# NRF24L01_LCD5110.net
KiCad netlist of a schematic drawn in EAGLE
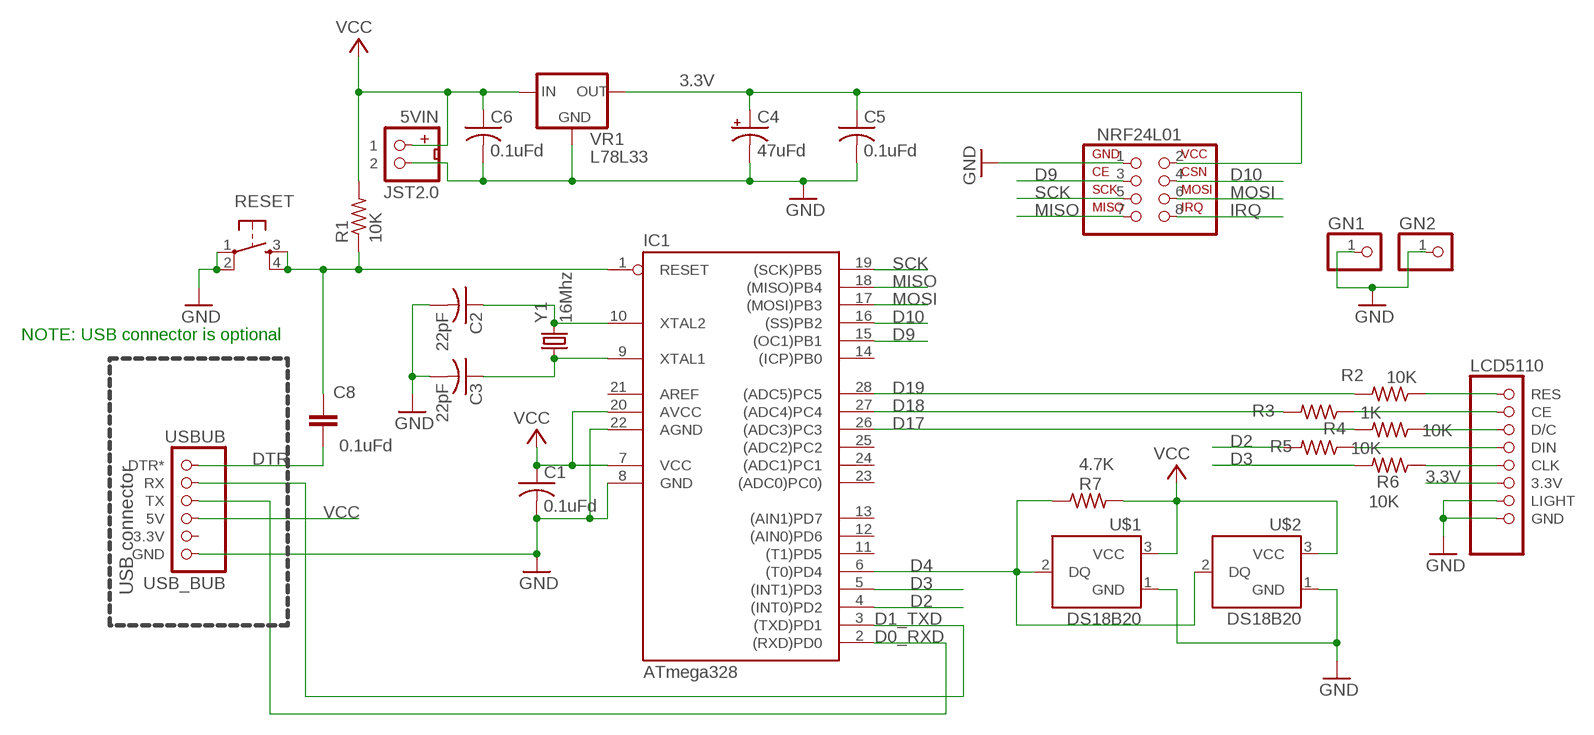
[diagram p0: schematic, sheet 1]

(export (version "E")
  (design (tool "Eeschema 10.0.6"))
  (components
    (comp (ref "5VIN")
      (value "JST2.0")
      (footprint "eagle-import:JST2.0")
      (libsource (lib "eagle-import") (part "JST2.0"))
    )
    (comp (ref "C1")
      (value "0.1uFd")
      (footprint "eagle-import:C050-025X075")
      (libsource (lib "eagle-import") (part "C-US050-025X075"))
    )
    (comp (ref "C2")
      (value "22pF")
      (footprint "eagle-import:C025-025X050")
      (libsource (lib "eagle-import") (part "C-US025-025X050"))
    )
    (comp (ref "C3")
      (value "22pF")
      (footprint "eagle-import:C025-025X050")
      (libsource (lib "eagle-import") (part "C-US025-025X050"))
    )
    (comp (ref "C4")
      (value "47uFd")
      (footprint "eagle-import:E2,5-6E")
      (libsource (lib "eagle-import") (part "CPOL-USE2,5-6E"))
    )
    (comp (ref "C5")
      (value "0.1uFd")
      (footprint "eagle-import:C025-025X050")
      (libsource (lib "eagle-import") (part "C-US025-025X050"))
    )
    (comp (ref "C6")
      (value "0.1uFd")
      (footprint "eagle-import:C050-025X075")
      (libsource (lib "eagle-import") (part "C-US050-025X075"))
    )
    (comp (ref "C8")
      (value "0.1uFd")
      (footprint "eagle-import:C050-025X075")
      (libsource (lib "eagle-import") (part "C-EU050-025X075"))
    )
    (comp (ref "GN1")
      (value "PINHD-1X1")
      (footprint "eagle-import:1X01")
      (libsource (lib "eagle-import") (part "PINHD-1X1"))
    )
    (comp (ref "GN2")
      (value "PINHD-1X1")
      (footprint "eagle-import:1X01")
      (libsource (lib "eagle-import") (part "PINHD-1X1"))
    )
    (comp (ref "IC1")
      (value "ATmega328")
      (footprint "eagle-import:DIL28-3")
      (libsource (lib "eagle-import") (part "AT90S4433P"))
    )
    (comp (ref "LCD5110")
      (value "LCD5110_1TOP")
      (footprint "eagle-import:LCD5110T1")
      (libsource (lib "eagle-import") (part "LCD5110_1TOP"))
    )
    (comp (ref "NRF24L01")
      (value "NRF24L01+")
      (footprint "eagle-import:NRF24L01+")
      (libsource (lib "eagle-import") (part "NRF24L01+"))
    )
    (comp (ref "R1")
      (value "10K")
      (footprint "eagle-import:0207_2V")
      (libsource (lib "eagle-import") (part "R-US_0207/2V"))
    )
    (comp (ref "R2")
      (value "10K")
      (footprint "eagle-import:0207_5V")
      (libsource (lib "eagle-import") (part "R-US_0207/5V"))
    )
    (comp (ref "R3")
      (value "1K")
      (footprint "eagle-import:0207_5V")
      (libsource (lib "eagle-import") (part "R-US_0207/5V"))
    )
    (comp (ref "R4")
      (value "10K")
      (footprint "eagle-import:0207_5V")
      (libsource (lib "eagle-import") (part "R-US_0207/5V"))
    )
    (comp (ref "R5")
      (value "10K")
      (footprint "eagle-import:0207_5V")
      (libsource (lib "eagle-import") (part "R-US_0207/5V"))
    )
    (comp (ref "R6")
      (value "10K")
      (footprint "eagle-import:0207_5V")
      (libsource (lib "eagle-import") (part "R-US_0207/5V"))
    )
    (comp (ref "R7")
      (value "4.7K")
      (footprint "eagle-import:0207_2V")
      (libsource (lib "eagle-import") (part "R-US_0207/2V"))
    )
    (comp (ref "RESET")
      (value "TAC_SWITCHPTH")
      (footprint "eagle-import:TACTILE-PTH")
      (libsource (lib "eagle-import") (part "TAC_SWITCHPTH"))
    )
    (comp (ref "U$1")
      (value "DS18B20")
      (footprint "eagle-import:DS18B20")
      (libsource (lib "eagle-import") (part "DS18B20"))
    )
    (comp (ref "U$2")
      (value "DS18B20")
      (footprint "eagle-import:DS18B20")
      (libsource (lib "eagle-import") (part "DS18B20"))
    )
    (comp (ref "USBUB")
      (value "USB_BUB")
      (footprint "eagle-import:USB_BUB")
      (libsource (lib "eagle-import") (part "USB_BUB"))
    )
    (comp (ref "VR1")
      (value "L78L33")
      (footprint "eagle-import:78LXX")
      (libsource (lib "eagle-import") (part "78LXX"))
    )
    (comp (ref "Y1")
      (value "16Mhz")
      (footprint "eagle-import:HC49US")
      (libsource (lib "eagle-import") (part "CRYSTALHC49US"))
    )
  )
  (nets
    (net (code "1") (name "/3.3V") (class "Default")
      (node (ref "C4") (pin "+") (pinfunction "+_+") (pintype "passive"))
      (node (ref "C5") (pin "1") (pinfunction "1_1") (pintype "passive"))
      (node (ref "LCD5110") (pin "3.3V") (pinfunction "3.3V_3.3V") (pintype "passive"))
      (node (ref "NRF24L01") (pin "2") (pinfunction "2_2") (pintype "passive"))
      (node (ref "VR1") (pin "OUT") (pinfunction "OUT_OUT") (pintype "passive"))
    )
    (net (code "2") (name "/D0_RXD") (class "Default")
      (node (ref "IC1") (pin "2") (pinfunction "(RXD)PD0_2") (pintype "bidirectional"))
      (node (ref "USBUB") (pin "TX") (pinfunction "TX_TX") (pintype "passive"))
    )
    (net (code "3") (name "/D1_TXD") (class "Default")
      (node (ref "IC1") (pin "3") (pinfunction "(TXD)PD1_3") (pintype "bidirectional"))
      (node (ref "USBUB") (pin "RX") (pinfunction "RX_RX") (pintype "passive"))
    )
    (net (code "4") (name "/D2") (class "Default")
      (node (ref "IC1") (pin "4") (pinfunction "(INT0)PD2_4") (pintype "bidirectional"))
      (node (ref "R5") (pin "2") (pinfunction "2_2") (pintype "passive"))
    )
    (net (code "5") (name "/D3") (class "Default")
      (node (ref "IC1") (pin "5") (pinfunction "(INT1)PD3_5") (pintype "bidirectional"))
      (node (ref "R6") (pin "2") (pinfunction "2_2") (pintype "passive"))
    )
    (net (code "6") (name "/D4") (class "Default")
      (node (ref "IC1") (pin "6") (pinfunction "(T0)PD4_6") (pintype "bidirectional"))
      (node (ref "R7") (pin "1") (pinfunction "1_1") (pintype "passive"))
      (node (ref "U$1") (pin "2") (pinfunction "DQ_2") (pintype "bidirectional"))
      (node (ref "U$2") (pin "2") (pinfunction "DQ_2") (pintype "bidirectional"))
    )
    (net (code "7") (name "/D9") (class "Default")
      (node (ref "IC1") (pin "15") (pinfunction "(OC1)PB1_15") (pintype "bidirectional"))
      (node (ref "NRF24L01") (pin "3") (pinfunction "3_3") (pintype "passive"))
    )
    (net (code "8") (name "/D10") (class "Default")
      (node (ref "IC1") (pin "16") (pinfunction "(SS)PB2_16") (pintype "bidirectional"))
      (node (ref "NRF24L01") (pin "4") (pinfunction "4_4") (pintype "passive"))
    )
    (net (code "9") (name "/D17") (class "Default")
      (node (ref "IC1") (pin "26") (pinfunction "(ADC3)PC3_26") (pintype "bidirectional"))
      (node (ref "R4") (pin "2") (pinfunction "2_2") (pintype "passive"))
    )
    (net (code "10") (name "/D18") (class "Default")
      (node (ref "IC1") (pin "27") (pinfunction "(ADC4)PC4_27") (pintype "bidirectional"))
      (node (ref "R3") (pin "2") (pinfunction "2_2") (pintype "passive"))
    )
    (net (code "11") (name "/D19") (class "Default")
      (node (ref "IC1") (pin "28") (pinfunction "(ADC5)PC5_28") (pintype "bidirectional"))
      (node (ref "R2") (pin "2") (pinfunction "2_2") (pintype "passive"))
    )
    (net (code "12") (name "/DTR") (class "Default")
      (node (ref "C8") (pin "1") (pinfunction "1_1") (pintype "passive"))
      (node (ref "USBUB") (pin "DTR*") (pinfunction "DTR*_DTR*") (pintype "passive"))
    )
    (net (code "13") (name "/IRQ") (class "Default")
      (node (ref "NRF24L01") (pin "8") (pinfunction "8_8") (pintype "passive"))
    )
    (net (code "14") (name "/MISO") (class "Default")
      (node (ref "IC1") (pin "18") (pinfunction "(MISO)PB4_18") (pintype "bidirectional"))
      (node (ref "NRF24L01") (pin "7") (pinfunction "7_7") (pintype "passive"))
    )
    (net (code "15") (name "/MOSI") (class "Default")
      (node (ref "IC1") (pin "17") (pinfunction "(MOSI)PB3_17") (pintype "bidirectional"))
      (node (ref "NRF24L01") (pin "6") (pinfunction "6_6") (pintype "passive"))
    )
    (net (code "16") (name "/SCK") (class "Default")
      (node (ref "IC1") (pin "19") (pinfunction "(SCK)PB5_19") (pintype "bidirectional"))
      (node (ref "NRF24L01") (pin "5") (pinfunction "5_5") (pintype "passive"))
    )
    (net (code "17") (name "GND") (class "Default")
      (node (ref "5VIN") (pin "2") (pinfunction "2_2") (pintype "passive"))
      (node (ref "C1") (pin "2") (pinfunction "2_2") (pintype "passive"))
      (node (ref "C2") (pin "2") (pinfunction "2_2") (pintype "passive"))
      (node (ref "C3") (pin "2") (pinfunction "2_2") (pintype "passive"))
      (node (ref "C4") (pin "-") (pinfunction "-_-") (pintype "passive"))
      (node (ref "C5") (pin "2") (pinfunction "2_2") (pintype "passive"))
      (node (ref "C6") (pin "2") (pinfunction "2_2") (pintype "passive"))
      (node (ref "GN1") (pin "1") (pinfunction "1_1") (pintype "passive"))
      (node (ref "GN2") (pin "1") (pinfunction "1_1") (pintype "passive"))
      (node (ref "IC1") (pin "22") (pinfunction "AGND_22") (pintype "power_in"))
      (node (ref "IC1") (pin "8") (pinfunction "GND_8") (pintype "power_in"))
      (node (ref "LCD5110") (pin "GND") (pinfunction "GND_GND") (pintype "passive"))
      (node (ref "LCD5110") (pin "LIGHT") (pinfunction "LIGHT_LIGHT") (pintype "passive"))
      (node (ref "NRF24L01") (pin "1") (pinfunction "1_1") (pintype "passive"))
      (node (ref "RESET") (pin "1") (pinfunction "1_1") (pintype "passive"))
      (node (ref "RESET") (pin "2") (pinfunction "2_2") (pintype "passive"))
      (node (ref "U$1") (pin "1") (pinfunction "GND_1") (pintype "bidirectional"))
      (node (ref "U$2") (pin "1") (pinfunction "GND_1") (pintype "bidirectional"))
      (node (ref "USBUB") (pin "GND") (pinfunction "GND_GND") (pintype "passive"))
      (node (ref "VR1") (pin "GND") (pinfunction "GND_GND") (pintype "input"))
    )
    (net (code "18") (name "Net-(IC1-RESET)") (class "Default")
      (node (ref "C8") (pin "2") (pinfunction "2_2") (pintype "passive"))
      (node (ref "IC1") (pin "1") (pinfunction "RESET_1") (pintype "input"))
      (node (ref "R1") (pin "1") (pinfunction "1_1") (pintype "passive"))
      (node (ref "RESET") (pin "3") (pinfunction "3_3") (pintype "passive"))
      (node (ref "RESET") (pin "4") (pinfunction "4_4") (pintype "passive"))
    )
    (net (code "19") (name "Net-(IC1-XTAL1)") (class "Default")
      (node (ref "C3") (pin "1") (pinfunction "1_1") (pintype "passive"))
      (node (ref "IC1") (pin "9") (pinfunction "XTAL1_9") (pintype "bidirectional"))
      (node (ref "Y1") (pin "1") (pinfunction "1_1") (pintype "passive"))
    )
    (net (code "20") (name "Net-(IC1-XTAL2)") (class "Default")
      (node (ref "C2") (pin "1") (pinfunction "1_1") (pintype "passive"))
      (node (ref "IC1") (pin "10") (pinfunction "XTAL2_10") (pintype "bidirectional"))
      (node (ref "Y1") (pin "2") (pinfunction "2_2") (pintype "passive"))
    )
    (net (code "21") (name "Net-(LCD5110-PadCE)") (class "Default")
      (node (ref "LCD5110") (pin "CE") (pinfunction "CE_CE") (pintype "passive"))
      (node (ref "R3") (pin "1") (pinfunction "1_1") (pintype "passive"))
    )
    (net (code "22") (name "Net-(LCD5110-PadCLK)") (class "Default")
      (node (ref "LCD5110") (pin "CLK") (pinfunction "CLK_CLK") (pintype "passive"))
      (node (ref "R6") (pin "1") (pinfunction "1_1") (pintype "passive"))
    )
    (net (code "23") (name "Net-(LCD5110-PadDIN)") (class "Default")
      (node (ref "LCD5110") (pin "DIN") (pinfunction "DIN_DIN") (pintype "passive"))
      (node (ref "R5") (pin "1") (pinfunction "1_1") (pintype "passive"))
    )
    (net (code "24") (name "Net-(LCD5110-PadD{slash}C)") (class "Default")
      (node (ref "LCD5110") (pin "D/C") (pinfunction "D/C_D/C") (pintype "passive"))
      (node (ref "R4") (pin "1") (pinfunction "1_1") (pintype "passive"))
    )
    (net (code "25") (name "Net-(LCD5110-PadRES)") (class "Default")
      (node (ref "LCD5110") (pin "RES") (pinfunction "RES_RES") (pintype "passive"))
      (node (ref "R2") (pin "1") (pinfunction "1_1") (pintype "passive"))
    )
    (net (code "26") (name "VCC") (class "Default")
      (node (ref "5VIN") (pin "1") (pinfunction "1_1") (pintype "passive"))
      (node (ref "C1") (pin "1") (pinfunction "1_1") (pintype "passive"))
      (node (ref "C6") (pin "1") (pinfunction "1_1") (pintype "passive"))
      (node (ref "IC1") (pin "20") (pinfunction "AVCC_20") (pintype "power_in"))
      (node (ref "IC1") (pin "7") (pinfunction "VCC_7") (pintype "power_in"))
      (node (ref "R1") (pin "2") (pinfunction "2_2") (pintype "passive"))
      (node (ref "R7") (pin "2") (pinfunction "2_2") (pintype "passive"))
      (node (ref "U$1") (pin "3") (pinfunction "VCC_3") (pintype "bidirectional"))
      (node (ref "U$2") (pin "3") (pinfunction "VCC_3") (pintype "bidirectional"))
      (node (ref "USBUB") (pin "5V") (pinfunction "5V_5V") (pintype "passive"))
      (node (ref "VR1") (pin "IN") (pinfunction "IN_IN") (pintype "input"))
    )
    (net (code "27") (name "unconnected-(IC1-(ADC0)PC0)-Pad23)") (class "Default")
      (node (ref "IC1") (pin "23") (pinfunction "(ADC0)PC0)_23") (pintype "bidirectional"))
    )
    (net (code "28") (name "unconnected-(IC1-(ADC1)PC1-Pad24)") (class "Default")
      (node (ref "IC1") (pin "24") (pinfunction "(ADC1)PC1_24") (pintype "bidirectional"))
    )
    (net (code "29") (name "unconnected-(IC1-(ADC2)PC2-Pad25)") (class "Default")
      (node (ref "IC1") (pin "25") (pinfunction "(ADC2)PC2_25") (pintype "bidirectional"))
    )
    (net (code "30") (name "unconnected-(IC1-(AIN0)PD6-Pad12)") (class "Default")
      (node (ref "IC1") (pin "12") (pinfunction "(AIN0)PD6_12") (pintype "bidirectional"))
    )
    (net (code "31") (name "unconnected-(IC1-(AIN1)PD7-Pad13)") (class "Default")
      (node (ref "IC1") (pin "13") (pinfunction "(AIN1)PD7_13") (pintype "bidirectional"))
    )
    (net (code "32") (name "unconnected-(IC1-(ICP)PB0-Pad14)") (class "Default")
      (node (ref "IC1") (pin "14") (pinfunction "(ICP)PB0_14") (pintype "bidirectional"))
    )
    (net (code "33") (name "unconnected-(IC1-(T1)PD5-Pad11)") (class "Default")
      (node (ref "IC1") (pin "11") (pinfunction "(T1)PD5_11") (pintype "bidirectional"))
    )
    (net (code "34") (name "unconnected-(IC1-AREF-Pad21)") (class "Default")
      (node (ref "IC1") (pin "21") (pinfunction "AREF_21") (pintype "passive"))
    )
    (net (code "35") (name "unconnected-(USBUB-Pad3.3V)") (class "Default")
      (node (ref "USBUB") (pin "3.3V") (pinfunction "3.3V_3.3V") (pintype "passive"))
    )
  )
)
